# power-volume-video-switching.net
KiCad netlist of a schematic drawn in EAGLE
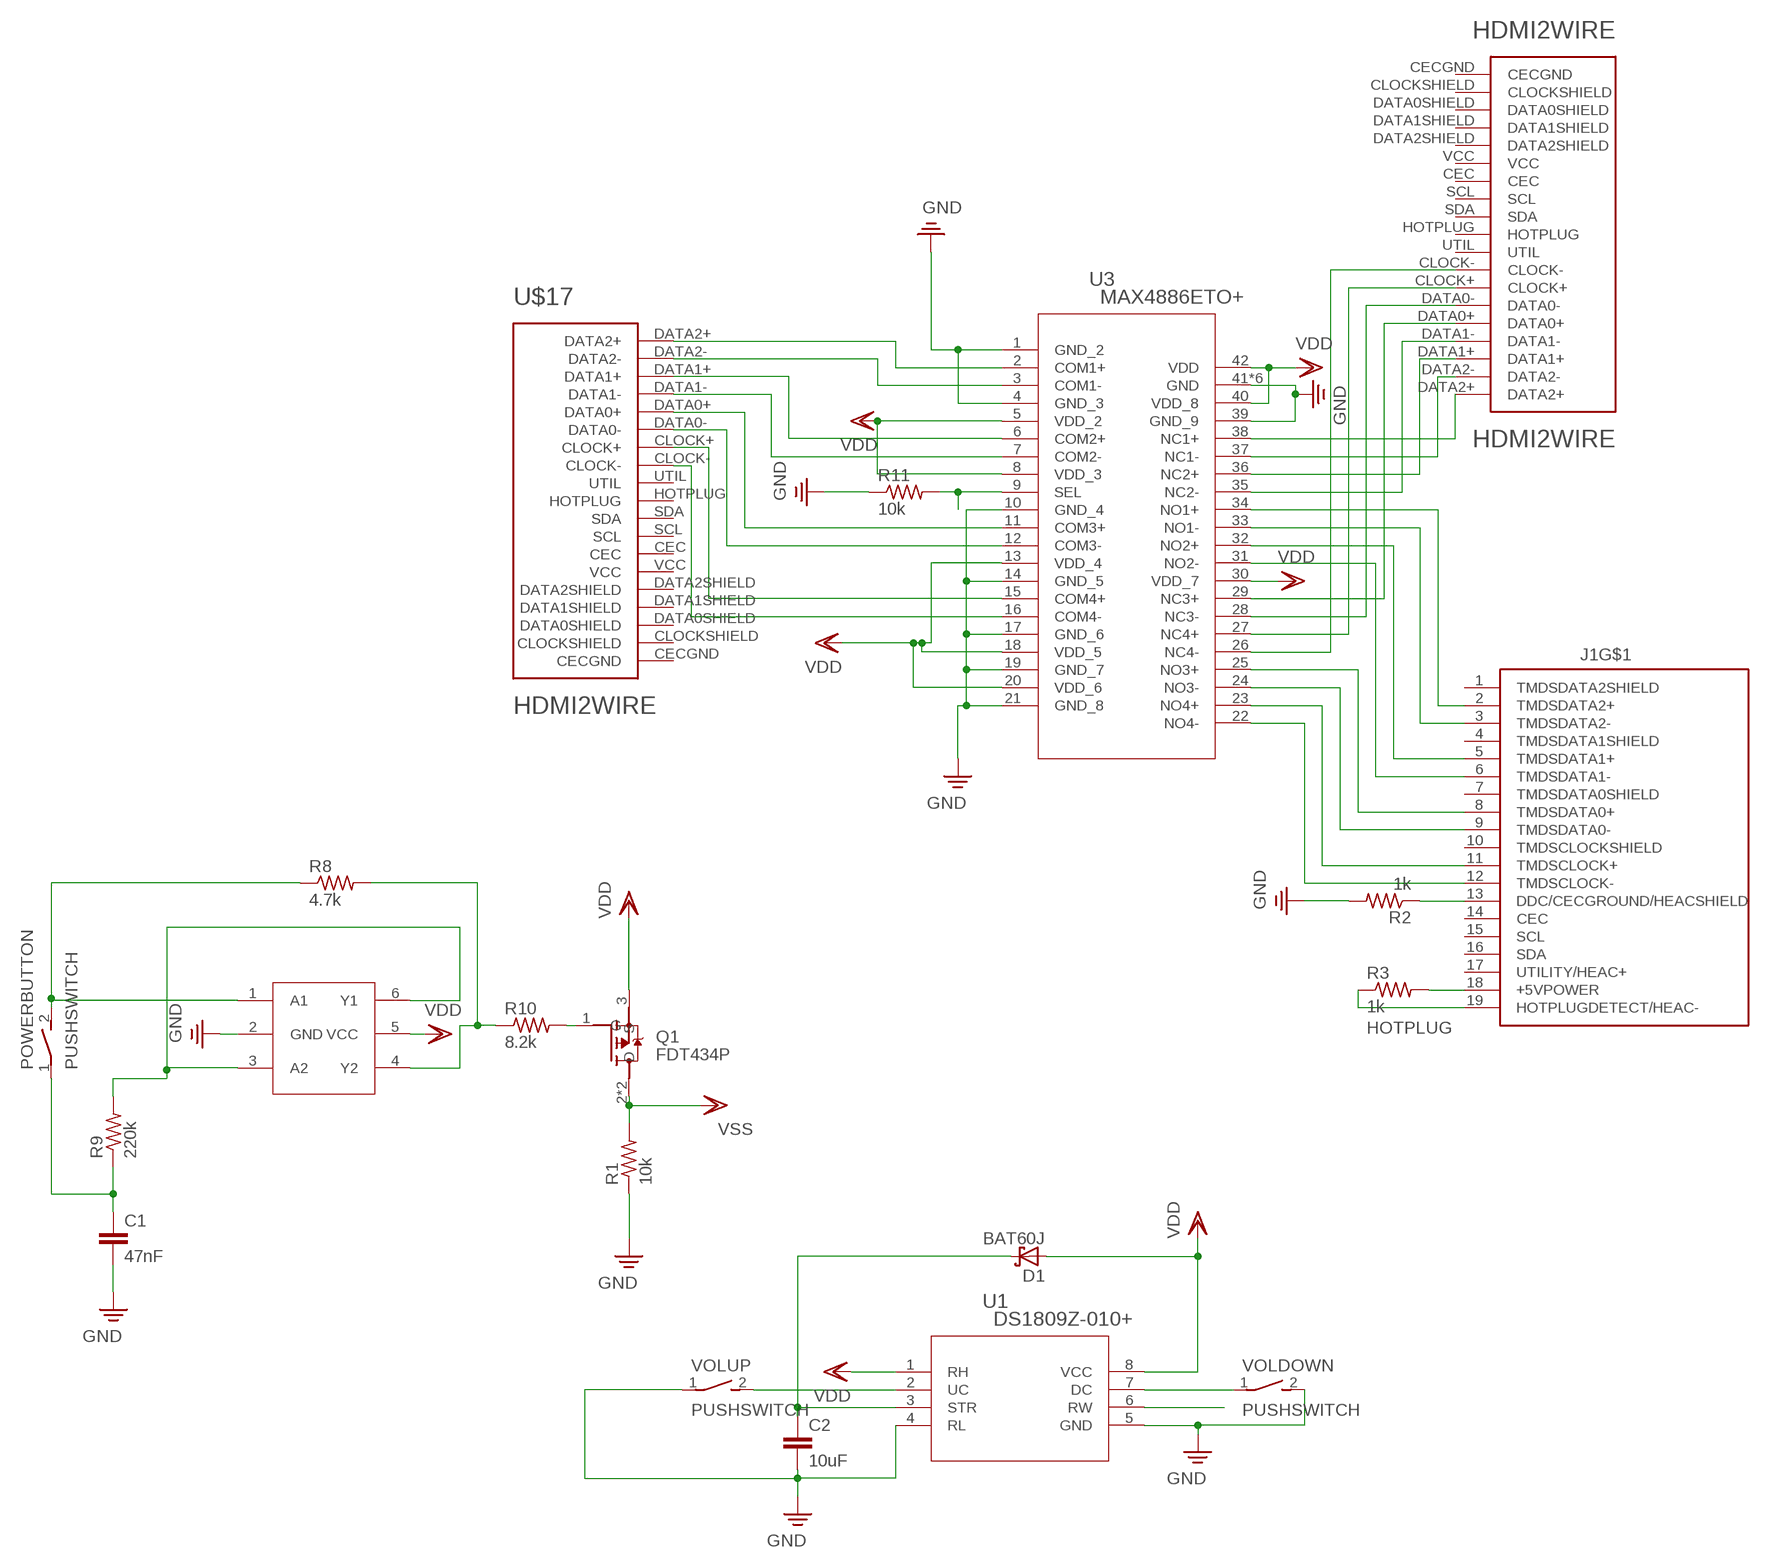
[diagram p0: schematic, sheet 1]

(export (version "E")
  (design (tool "Eeschema 10.0.6"))
  (components
    (comp (ref "C1")
      (value "47nF")
      (footprint "eagle-import:C0603")
      (libsource (lib "eagle-import") (part "resistor_348_C-EUC0603"))
    )
    (comp (ref "C2")
      (value "10uF")
      (footprint "eagle-import:C0603")
      (libsource (lib "eagle-import") (part "C-EUC0603"))
    )
    (comp (ref "D1")
      (value "BAT60J")
      (footprint "eagle-import:SOD323_ST")
      (libsource (lib "eagle-import") (part "BAT60J"))
    )
    (comp (ref "HDMI2WIRE")
      (value "HDMI2WIRE")
      (footprint "eagle-import:HDMI")
      (libsource (lib "eagle-import") (part "HDMI2WIRE"))
    )
    (comp (ref "J1")
      (value "685119136923")
      (footprint "eagle-import:685119136923")
      (libsource (lib "eagle-import") (part "685119136923"))
    )
    (comp (ref "POWERBUTTON")
      (value "PUSHSWITCH")
      (footprint "eagle-import:PUSHSWITCH")
      (libsource (lib "eagle-import") (part "PUSHSWITCH"))
    )
    (comp (ref "Q1")
      (value "FDT434P")
      (footprint "eagle-import:SOT230P700X180-4N")
      (fields (field (name "DIGI-KEY_PART_NUMBER") "FDT434PCT-ND") (field (name "MF") "ON Semiconductor"))
      (libsource (lib "eagle-import") (part "FDT434P"))
    )
    (comp (ref "R1")
      (value "10k")
      (footprint "eagle-import:R0603")
      (libsource (lib "eagle-import") (part "R-US_R0603"))
    )
    (comp (ref "R2")
      (value "1k")
      (footprint "eagle-import:R0603")
      (libsource (lib "eagle-import") (part "R-US_R0603"))
    )
    (comp (ref "R3")
      (value "1k")
      (footprint "eagle-import:R0603")
      (libsource (lib "eagle-import") (part "R-US_R0603"))
    )
    (comp (ref "R8")
      (value "4.7k")
      (footprint "eagle-import:R0603")
      (libsource (lib "eagle-import") (part "R-US_R0603"))
    )
    (comp (ref "R9")
      (value "220k")
      (footprint "eagle-import:R0603")
      (libsource (lib "eagle-import") (part "R-US_R0603"))
    )
    (comp (ref "R10")
      (value "8.2k")
      (footprint "eagle-import:R0603")
      (libsource (lib "eagle-import") (part "R-US_R0603"))
    )
    (comp (ref "R11")
      (value "10k")
      (footprint "eagle-import:R0603")
      (libsource (lib "eagle-import") (part "R-US_R0603"))
    )
    (comp (ref "U$17")
      (value "HDMI2WIRE")
      (footprint "eagle-import:HDMI")
      (libsource (lib "eagle-import") (part "HDMI2WIRE"))
    )
    (comp (ref "U1")
      (value "DS1809Z-010+")
      (footprint "eagle-import:21-0041B_8")
      (fields (field (name "MANUFACTURER_PART_NUMBER") "DS1809Z010+"))
      (libsource (lib "eagle-import") (part "DS1809Z-010+"))
    )
    (comp (ref "U2")
      (value "NC7WZ14P6X")
      (footprint "eagle-import:SC70-6L")
      (libsource (lib "eagle-import") (part "NC7WZ14P6X"))
    )
    (comp (ref "U3")
      (value "MAX4886ETO+")
      (footprint "eagle-import:21-0181B_T423590M-1")
      (libsource (lib "eagle-import") (part "MAX4886ETO+"))
    )
    (comp (ref "VOLDOWN")
      (value "PUSHSWITCH")
      (footprint "eagle-import:PUSHSWITCH")
      (libsource (lib "eagle-import") (part "PUSHSWITCH"))
    )
    (comp (ref "VOLUP")
      (value "PUSHSWITCH")
      (footprint "eagle-import:PUSHSWITCH")
      (libsource (lib "eagle-import") (part "PUSHSWITCH"))
    )
  )
  (nets
    (net (code "1") (name "/HOTPLUG") (class "Default")
      (node (ref "J1") (pin "19") (pinfunction "HOTPLUGDETECT/HEAC-_19") (pintype "passive"))
      (node (ref "R11") (pin "2") (pinfunction "2_2") (pintype "passive"))
      (node (ref "R3") (pin "1") (pinfunction "1_1") (pintype "passive"))
      (node (ref "U3") (pin "9") (pinfunction "SEL_9") (pintype "input"))
    )
    (net (code "2") (name "GND") (class "Default")
      (node (ref "C1") (pin "2") (pinfunction "2_2") (pintype "passive"))
      (node (ref "C2") (pin "2") (pinfunction "2_2") (pintype "passive"))
      (node (ref "R1") (pin "1") (pinfunction "1_1") (pintype "passive"))
      (node (ref "R11") (pin "1") (pinfunction "1_1") (pintype "passive"))
      (node (ref "R2") (pin "2") (pinfunction "2_2") (pintype "passive"))
      (node (ref "U1") (pin "4") (pinfunction "RL_4") (pintype "passive"))
      (node (ref "U1") (pin "5") (pinfunction "GND_5") (pintype "power_in"))
      (node (ref "U2") (pin "2") (pinfunction "GND_2") (pintype "bidirectional"))
      (node (ref "U3") (pin "1") (pinfunction "GND_2_1") (pintype "power_in"))
      (node (ref "U3") (pin "10") (pinfunction "GND_4_10") (pintype "power_in"))
      (node (ref "U3") (pin "14") (pinfunction "GND_5_14") (pintype "power_in"))
      (node (ref "U3") (pin "17") (pinfunction "GND_6_17") (pintype "power_in"))
      (node (ref "U3") (pin "19") (pinfunction "GND_7_19") (pintype "power_in"))
      (node (ref "U3") (pin "21") (pinfunction "GND_8_21") (pintype "power_in"))
      (node (ref "U3") (pin "39") (pinfunction "GND_9_39") (pintype "power_in"))
      (node (ref "U3") (pin "4") (pinfunction "GND_3_4") (pintype "power_in"))
      (node (ref "U3") (pin "41") (pinfunction "GND_41") (pintype "power_in"))
      (node (ref "U3") (pin "43") (pinfunction "GND_43") (pintype "power_in"))
      (node (ref "U3") (pin "P$1") (pinfunction "GND_P$1") (pintype "power_in"))
      (node (ref "U3") (pin "P$2") (pinfunction "GND_P$2") (pintype "power_in"))
      (node (ref "U3") (pin "P$3") (pinfunction "GND_P$3") (pintype "power_in"))
      (node (ref "U3") (pin "P$4") (pinfunction "GND_P$4") (pintype "power_in"))
      (node (ref "VOLDOWN") (pin "2") (pinfunction "S_2") (pintype "passive"))
      (node (ref "VOLUP") (pin "1") (pinfunction "P_1") (pintype "passive"))
    )
    (net (code "3") (name "Net-(J1A-+5VPOWER)") (class "Default")
      (node (ref "J1") (pin "18") (pinfunction "+5VPOWER_18") (pintype "power_in"))
      (node (ref "R3") (pin "2") (pinfunction "2_2") (pintype "passive"))
    )
    (net (code "4") (name "Net-(J1A-DDC{slash}CECGROUND{slash}HEACSHIELD)") (class "Default")
      (node (ref "J1") (pin "13") (pinfunction "DDC/CECGROUND/HEACSHIELD_13") (pintype "passive"))
      (node (ref "R2") (pin "1") (pinfunction "1_1") (pintype "passive"))
    )
    (net (code "5") (name "Net-(J1A-TMDSCLOCK+)") (class "Default")
      (node (ref "J1") (pin "11") (pinfunction "TMDSCLOCK+_11") (pintype "passive"))
      (node (ref "U3") (pin "23") (pinfunction "NO4+_23") (pintype "bidirectional"))
    )
    (net (code "6") (name "Net-(J1A-TMDSCLOCK-)") (class "Default")
      (node (ref "J1") (pin "12") (pinfunction "TMDSCLOCK-_12") (pintype "passive"))
      (node (ref "U3") (pin "22") (pinfunction "NO4-_22") (pintype "bidirectional"))
    )
    (net (code "7") (name "Net-(J1A-TMDSDATA0+)") (class "Default")
      (node (ref "J1") (pin "8") (pinfunction "TMDSDATA0+_8") (pintype "passive"))
      (node (ref "U3") (pin "25") (pinfunction "NO3+_25") (pintype "bidirectional"))
    )
    (net (code "8") (name "Net-(J1A-TMDSDATA0-)") (class "Default")
      (node (ref "J1") (pin "9") (pinfunction "TMDSDATA0-_9") (pintype "passive"))
      (node (ref "U3") (pin "24") (pinfunction "NO3-_24") (pintype "bidirectional"))
    )
    (net (code "9") (name "Net-(J1A-TMDSDATA1+)") (class "Default")
      (node (ref "J1") (pin "5") (pinfunction "TMDSDATA1+_5") (pintype "passive"))
      (node (ref "U3") (pin "32") (pinfunction "NO2+_32") (pintype "bidirectional"))
    )
    (net (code "10") (name "Net-(J1A-TMDSDATA1-)") (class "Default")
      (node (ref "J1") (pin "6") (pinfunction "TMDSDATA1-_6") (pintype "passive"))
      (node (ref "U3") (pin "31") (pinfunction "NO2-_31") (pintype "bidirectional"))
    )
    (net (code "11") (name "Net-(J1A-TMDSDATA2+)") (class "Default")
      (node (ref "J1") (pin "2") (pinfunction "TMDSDATA2+_2") (pintype "passive"))
      (node (ref "U3") (pin "34") (pinfunction "NO1+_34") (pintype "bidirectional"))
    )
    (net (code "12") (name "Net-(J1A-TMDSDATA2-)") (class "Default")
      (node (ref "J1") (pin "3") (pinfunction "TMDSDATA2-_3") (pintype "passive"))
      (node (ref "U3") (pin "33") (pinfunction "NO1-_33") (pintype "bidirectional"))
    )
    (net (code "13") (name "Net-(POWERBUTTON-P)") (class "Default")
      (node (ref "C1") (pin "1") (pinfunction "1_1") (pintype "passive"))
      (node (ref "POWERBUTTON") (pin "1") (pinfunction "P_1") (pintype "passive"))
      (node (ref "R9") (pin "1") (pinfunction "1_1") (pintype "passive"))
    )
    (net (code "14") (name "Net-(POWERBUTTON-S)") (class "Default")
      (node (ref "POWERBUTTON") (pin "2") (pinfunction "S_2") (pintype "passive"))
      (node (ref "R8") (pin "1") (pinfunction "1_1") (pintype "passive"))
      (node (ref "U2") (pin "1") (pinfunction "A1_1") (pintype "bidirectional"))
    )
    (net (code "15") (name "Net-(Q1-G)") (class "Default")
      (node (ref "Q1") (pin "1") (pinfunction "G_1") (pintype "passive"))
      (node (ref "R10") (pin "2") (pinfunction "2_2") (pintype "passive"))
    )
    (net (code "16") (name "Net-(U1-DC)") (class "Default")
      (node (ref "U1") (pin "7") (pinfunction "DC_7") (pintype "input"))
      (node (ref "VOLDOWN") (pin "1") (pinfunction "P_1") (pintype "passive"))
    )
    (net (code "17") (name "Net-(U1-STR)") (class "Default")
      (node (ref "C2") (pin "1") (pinfunction "1_1") (pintype "passive"))
      (node (ref "D1") (pin "C") (pinfunction "C_C") (pintype "passive"))
      (node (ref "U1") (pin "3") (pinfunction "STR_3") (pintype "input"))
    )
    (net (code "18") (name "Net-(U1-UC)") (class "Default")
      (node (ref "U1") (pin "2") (pinfunction "UC_2") (pintype "input"))
      (node (ref "VOLUP") (pin "2") (pinfunction "S_2") (pintype "passive"))
    )
    (net (code "19") (name "Net-(U2-A2)") (class "Default")
      (node (ref "R9") (pin "2") (pinfunction "2_2") (pintype "passive"))
      (node (ref "U2") (pin "3") (pinfunction "A2_3") (pintype "bidirectional"))
      (node (ref "U2") (pin "6") (pinfunction "Y1_6") (pintype "bidirectional"))
    )
    (net (code "20") (name "Net-(U2-Y2)") (class "Default")
      (node (ref "R10") (pin "1") (pinfunction "1_1") (pintype "passive"))
      (node (ref "R8") (pin "2") (pinfunction "2_2") (pintype "passive"))
      (node (ref "U2") (pin "4") (pinfunction "Y2_4") (pintype "bidirectional"))
    )
    (net (code "21") (name "Net-(U3-COM1+)") (class "Default")
      (node (ref "U$17") (pin "DATA2+") (pinfunction "DATA2+_DATA2+") (pintype "bidirectional"))
      (node (ref "U3") (pin "2") (pinfunction "COM1+_2") (pintype "bidirectional"))
    )
    (net (code "22") (name "Net-(U3-COM1-)") (class "Default")
      (node (ref "U$17") (pin "DATA2-") (pinfunction "DATA2-_DATA2-") (pintype "bidirectional"))
      (node (ref "U3") (pin "3") (pinfunction "COM1-_3") (pintype "bidirectional"))
    )
    (net (code "23") (name "Net-(U3-COM2+)") (class "Default")
      (node (ref "U$17") (pin "DATA1+") (pinfunction "DATA1+_DATA1+") (pintype "bidirectional"))
      (node (ref "U3") (pin "6") (pinfunction "COM2+_6") (pintype "bidirectional"))
    )
    (net (code "24") (name "Net-(U3-COM2-)") (class "Default")
      (node (ref "U$17") (pin "DATA1-") (pinfunction "DATA1-_DATA1-") (pintype "bidirectional"))
      (node (ref "U3") (pin "7") (pinfunction "COM2-_7") (pintype "bidirectional"))
    )
    (net (code "25") (name "Net-(U3-COM3+)") (class "Default")
      (node (ref "U$17") (pin "DATA0+") (pinfunction "DATA0+_DATA0+") (pintype "bidirectional"))
      (node (ref "U3") (pin "11") (pinfunction "COM3+_11") (pintype "bidirectional"))
    )
    (net (code "26") (name "Net-(U3-COM3-)") (class "Default")
      (node (ref "U$17") (pin "DATA0-") (pinfunction "DATA0-_DATA0-") (pintype "bidirectional"))
      (node (ref "U3") (pin "12") (pinfunction "COM3-_12") (pintype "bidirectional"))
    )
    (net (code "27") (name "Net-(U3-COM4+)") (class "Default")
      (node (ref "U$17") (pin "CLOCK+") (pinfunction "CLOCK+_CLOCK+") (pintype "bidirectional"))
      (node (ref "U3") (pin "15") (pinfunction "COM4+_15") (pintype "bidirectional"))
    )
    (net (code "28") (name "Net-(U3-COM4-)") (class "Default")
      (node (ref "U$17") (pin "CLOCK-") (pinfunction "CLOCK-_CLOCK-") (pintype "bidirectional"))
      (node (ref "U3") (pin "16") (pinfunction "COM4-_16") (pintype "bidirectional"))
    )
    (net (code "29") (name "Net-(U3-NC1+)") (class "Default")
      (node (ref "HDMI2WIRE") (pin "DATA2+") (pinfunction "DATA2+_DATA2+") (pintype "bidirectional"))
      (node (ref "U3") (pin "38") (pinfunction "NC1+_38") (pintype "bidirectional"))
    )
    (net (code "30") (name "Net-(U3-NC1-)") (class "Default")
      (node (ref "HDMI2WIRE") (pin "DATA2-") (pinfunction "DATA2-_DATA2-") (pintype "bidirectional"))
      (node (ref "U3") (pin "37") (pinfunction "NC1-_37") (pintype "bidirectional"))
    )
    (net (code "31") (name "Net-(U3-NC2+)") (class "Default")
      (node (ref "HDMI2WIRE") (pin "DATA1+") (pinfunction "DATA1+_DATA1+") (pintype "bidirectional"))
      (node (ref "U3") (pin "36") (pinfunction "NC2+_36") (pintype "bidirectional"))
    )
    (net (code "32") (name "Net-(U3-NC2-)") (class "Default")
      (node (ref "HDMI2WIRE") (pin "DATA1-") (pinfunction "DATA1-_DATA1-") (pintype "bidirectional"))
      (node (ref "U3") (pin "35") (pinfunction "NC2-_35") (pintype "bidirectional"))
    )
    (net (code "33") (name "Net-(U3-NC3+)") (class "Default")
      (node (ref "HDMI2WIRE") (pin "DATA0+") (pinfunction "DATA0+_DATA0+") (pintype "bidirectional"))
      (node (ref "U3") (pin "29") (pinfunction "NC3+_29") (pintype "bidirectional"))
    )
    (net (code "34") (name "Net-(U3-NC3-)") (class "Default")
      (node (ref "HDMI2WIRE") (pin "DATA0-") (pinfunction "DATA0-_DATA0-") (pintype "bidirectional"))
      (node (ref "U3") (pin "28") (pinfunction "NC3-_28") (pintype "bidirectional"))
    )
    (net (code "35") (name "Net-(U3-NC4+)") (class "Default")
      (node (ref "HDMI2WIRE") (pin "CLOCK+") (pinfunction "CLOCK+_CLOCK+") (pintype "bidirectional"))
      (node (ref "U3") (pin "27") (pinfunction "NC4+_27") (pintype "bidirectional"))
    )
    (net (code "36") (name "Net-(U3-NC4-)") (class "Default")
      (node (ref "HDMI2WIRE") (pin "CLOCK-") (pinfunction "CLOCK-_CLOCK-") (pintype "bidirectional"))
      (node (ref "U3") (pin "26") (pinfunction "NC4-_26") (pintype "bidirectional"))
    )
    (net (code "37") (name "VDD") (class "Default")
      (node (ref "D1") (pin "A") (pinfunction "A_A") (pintype "passive"))
      (node (ref "Q1") (pin "3") (pinfunction "S_3") (pintype "passive"))
      (node (ref "U1") (pin "1") (pinfunction "RH_1") (pintype "passive"))
      (node (ref "U1") (pin "8") (pinfunction "VCC_8") (pintype "power_in"))
      (node (ref "U2") (pin "5") (pinfunction "VCC_5") (pintype "bidirectional"))
      (node (ref "U3") (pin "13") (pinfunction "VDD_4_13") (pintype "power_in"))
      (node (ref "U3") (pin "18") (pinfunction "VDD_5_18") (pintype "power_in"))
      (node (ref "U3") (pin "20") (pinfunction "VDD_6_20") (pintype "power_in"))
      (node (ref "U3") (pin "30") (pinfunction "VDD_7_30") (pintype "power_in"))
      (node (ref "U3") (pin "40") (pinfunction "VDD_8_40") (pintype "power_in"))
      (node (ref "U3") (pin "42") (pinfunction "VDD_42") (pintype "power_in"))
      (node (ref "U3") (pin "5") (pinfunction "VDD_2_5") (pintype "power_in"))
      (node (ref "U3") (pin "8") (pinfunction "VDD_3_8") (pintype "power_in"))
    )
    (net (code "38") (name "VSS") (class "Default")
      (node (ref "Q1") (pin "2") (pinfunction "D_2") (pintype "passive"))
      (node (ref "Q1") (pin "4") (pinfunction "D_4") (pintype "passive"))
      (node (ref "R1") (pin "2") (pinfunction "2_2") (pintype "passive"))
    )
    (net (code "39") (name "unconnected-(HDMI2WIRE-PadCEC)") (class "Default")
      (node (ref "HDMI2WIRE") (pin "CEC") (pinfunction "CEC_CEC") (pintype "bidirectional"))
    )
    (net (code "40") (name "unconnected-(HDMI2WIRE-PadCECGND)") (class "Default")
      (node (ref "HDMI2WIRE") (pin "CECGND") (pinfunction "CECGND_CECGND") (pintype "bidirectional"))
    )
    (net (code "41") (name "unconnected-(HDMI2WIRE-PadCLOCKSHIELD)") (class "Default")
      (node (ref "HDMI2WIRE") (pin "CLOCKSHIELD") (pinfunction "CLOCKSHIELD_CLOCKSHIELD") (pintype "bidirectional"))
    )
    (net (code "42") (name "unconnected-(HDMI2WIRE-PadDATA0SHIELD)") (class "Default")
      (node (ref "HDMI2WIRE") (pin "DATA0SHIELD") (pinfunction "DATA0SHIELD_DATA0SHIELD") (pintype "bidirectional"))
    )
    (net (code "43") (name "unconnected-(HDMI2WIRE-PadDATA1SHIELD)") (class "Default")
      (node (ref "HDMI2WIRE") (pin "DATA1SHIELD") (pinfunction "DATA1SHIELD_DATA1SHIELD") (pintype "bidirectional"))
    )
    (net (code "44") (name "unconnected-(HDMI2WIRE-PadDATA2SHIELD)") (class "Default")
      (node (ref "HDMI2WIRE") (pin "DATA2SHIELD") (pinfunction "DATA2SHIELD_DATA2SHIELD") (pintype "bidirectional"))
    )
    (net (code "45") (name "unconnected-(HDMI2WIRE-PadHOTPLUG)") (class "Default")
      (node (ref "HDMI2WIRE") (pin "HOTPLUG") (pinfunction "HOTPLUG_HOTPLUG") (pintype "bidirectional"))
    )
    (net (code "46") (name "unconnected-(HDMI2WIRE-PadSCL)") (class "Default")
      (node (ref "HDMI2WIRE") (pin "SCL") (pinfunction "SCL_SCL") (pintype "bidirectional"))
    )
    (net (code "47") (name "unconnected-(HDMI2WIRE-PadSDA)") (class "Default")
      (node (ref "HDMI2WIRE") (pin "SDA") (pinfunction "SDA_SDA") (pintype "bidirectional"))
    )
    (net (code "48") (name "unconnected-(HDMI2WIRE-PadUTIL)") (class "Default")
      (node (ref "HDMI2WIRE") (pin "UTIL") (pinfunction "UTIL_UTIL") (pintype "bidirectional"))
    )
    (net (code "49") (name "unconnected-(HDMI2WIRE-PadVCC)") (class "Default")
      (node (ref "HDMI2WIRE") (pin "VCC") (pinfunction "VCC_VCC") (pintype "bidirectional"))
    )
    (net (code "50") (name "unconnected-(J1A-CEC-Pad14)") (class "Default")
      (node (ref "J1") (pin "14") (pinfunction "CEC_14") (pintype "passive"))
    )
    (net (code "51") (name "unconnected-(J1A-SCL-Pad15)") (class "Default")
      (node (ref "J1") (pin "15") (pinfunction "SCL_15") (pintype "passive"))
    )
    (net (code "52") (name "unconnected-(J1A-SDA-Pad16)") (class "Default")
      (node (ref "J1") (pin "16") (pinfunction "SDA_16") (pintype "passive"))
    )
    (net (code "53") (name "unconnected-(J1A-TMDSCLOCKSHIELD-Pad10)") (class "Default")
      (node (ref "J1") (pin "10") (pinfunction "TMDSCLOCKSHIELD_10") (pintype "passive"))
    )
    (net (code "54") (name "unconnected-(J1A-TMDSDATA0SHIELD-Pad7)") (class "Default")
      (node (ref "J1") (pin "7") (pinfunction "TMDSDATA0SHIELD_7") (pintype "passive"))
    )
    (net (code "55") (name "unconnected-(J1A-TMDSDATA1SHIELD-Pad4)") (class "Default")
      (node (ref "J1") (pin "4") (pinfunction "TMDSDATA1SHIELD_4") (pintype "passive"))
    )
    (net (code "56") (name "unconnected-(J1A-TMDSDATA2SHIELD-Pad1)") (class "Default")
      (node (ref "J1") (pin "1") (pinfunction "TMDSDATA2SHIELD_1") (pintype "passive"))
    )
    (net (code "57") (name "unconnected-(J1A-UTILITY{slash}HEAC+-Pad17)") (class "Default")
      (node (ref "J1") (pin "17") (pinfunction "UTILITY/HEAC+_17") (pintype "passive"))
    )
    (net (code "58") (name "unconnected-(U$17-PadCEC)") (class "Default")
      (node (ref "U$17") (pin "CEC") (pinfunction "CEC_CEC") (pintype "bidirectional"))
    )
    (net (code "59") (name "unconnected-(U$17-PadCECGND)") (class "Default")
      (node (ref "U$17") (pin "CECGND") (pinfunction "CECGND_CECGND") (pintype "bidirectional"))
    )
    (net (code "60") (name "unconnected-(U$17-PadCLOCKSHIELD)") (class "Default")
      (node (ref "U$17") (pin "CLOCKSHIELD") (pinfunction "CLOCKSHIELD_CLOCKSHIELD") (pintype "bidirectional"))
    )
    (net (code "61") (name "unconnected-(U$17-PadDATA0SHIELD)") (class "Default")
      (node (ref "U$17") (pin "DATA0SHIELD") (pinfunction "DATA0SHIELD_DATA0SHIELD") (pintype "bidirectional"))
    )
    (net (code "62") (name "unconnected-(U$17-PadDATA1SHIELD)") (class "Default")
      (node (ref "U$17") (pin "DATA1SHIELD") (pinfunction "DATA1SHIELD_DATA1SHIELD") (pintype "bidirectional"))
    )
    (net (code "63") (name "unconnected-(U$17-PadDATA2SHIELD)") (class "Default")
      (node (ref "U$17") (pin "DATA2SHIELD") (pinfunction "DATA2SHIELD_DATA2SHIELD") (pintype "bidirectional"))
    )
    (net (code "64") (name "unconnected-(U$17-PadHOTPLUG)") (class "Default")
      (node (ref "U$17") (pin "HOTPLUG") (pinfunction "HOTPLUG_HOTPLUG") (pintype "bidirectional"))
    )
    (net (code "65") (name "unconnected-(U$17-PadSCL)") (class "Default")
      (node (ref "U$17") (pin "SCL") (pinfunction "SCL_SCL") (pintype "bidirectional"))
    )
    (net (code "66") (name "unconnected-(U$17-PadSDA)") (class "Default")
      (node (ref "U$17") (pin "SDA") (pinfunction "SDA_SDA") (pintype "bidirectional"))
    )
    (net (code "67") (name "unconnected-(U$17-PadUTIL)") (class "Default")
      (node (ref "U$17") (pin "UTIL") (pinfunction "UTIL_UTIL") (pintype "bidirectional"))
    )
    (net (code "68") (name "unconnected-(U$17-PadVCC)") (class "Default")
      (node (ref "U$17") (pin "VCC") (pinfunction "VCC_VCC") (pintype "bidirectional"))
    )
    (net (code "69") (name "unconnected-(U1-RW-Pad6)") (class "Default")
      (node (ref "U1") (pin "6") (pinfunction "RW_6") (pintype "passive"))
    )
  )
)
